# AirPi1-2.net
KiCad netlist of a schematic drawn in EAGLE
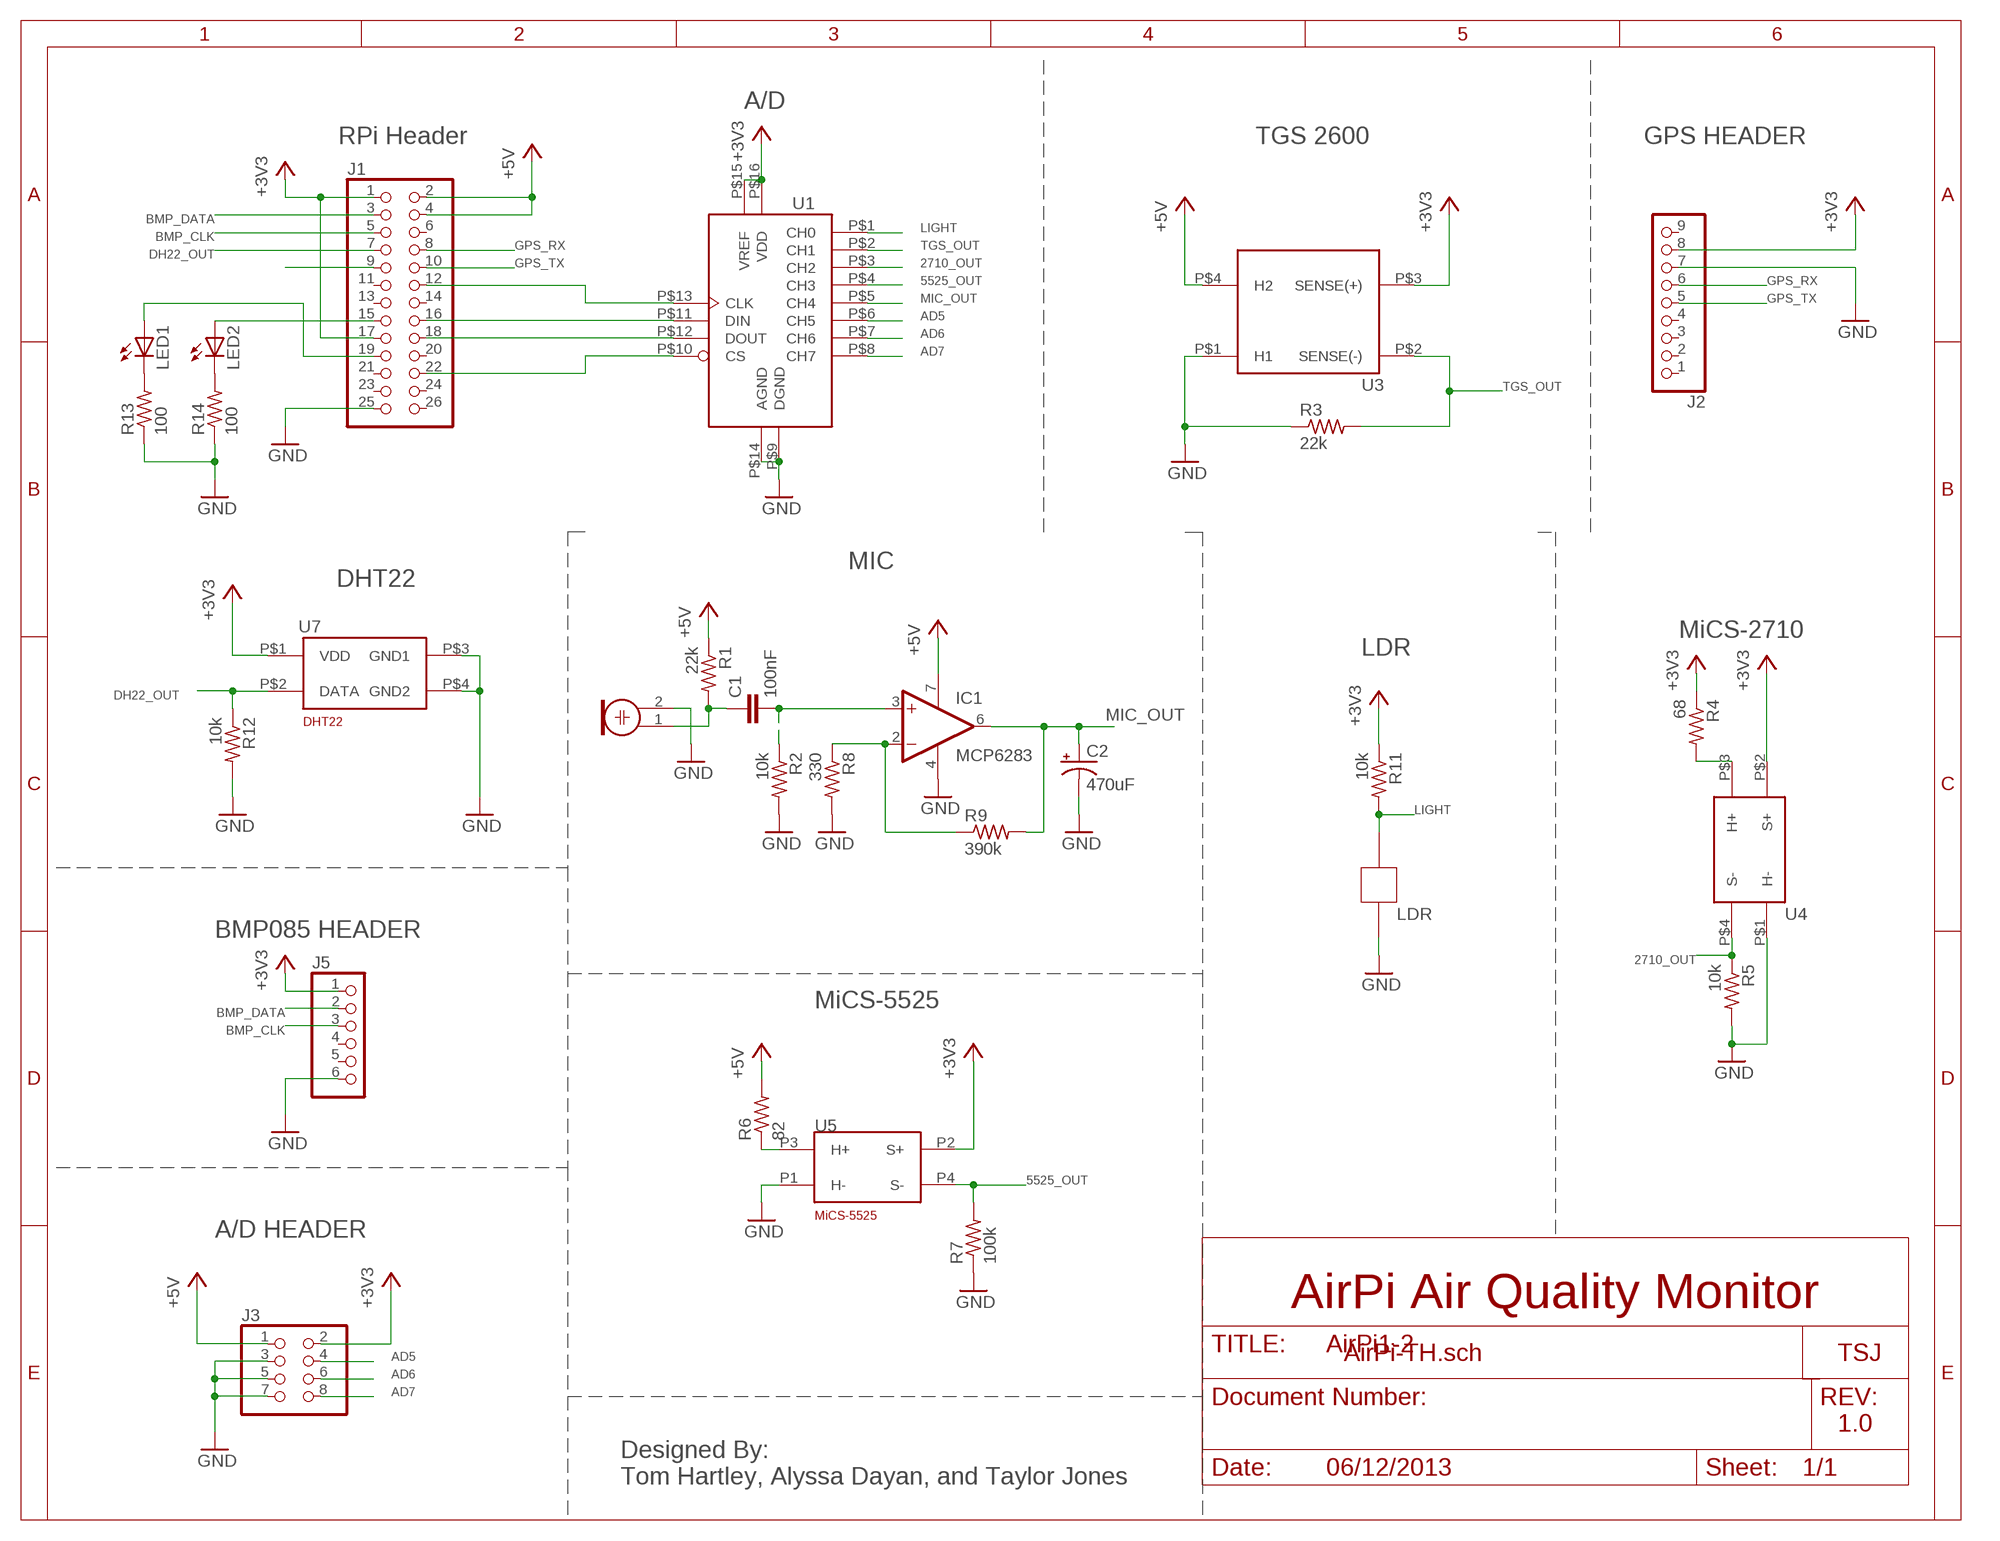
[diagram p0: schematic, sheet 1]

(export (version "E")
  (design (tool "Eeschema 10.0.6"))
  (components
    (comp (ref "C1")
      (value "100nF")
      (footprint "eagle-import:C2.5-4")
      (libsource (lib "eagle-import") (part "C2.5/4"))
    )
    (comp (ref "C2")
      (value "470uF")
      (footprint "eagle-import:E5-10,5")
      (libsource (lib "eagle-import") (part "CPOL-USE5-10.5"))
    )
    (comp (ref "IC1")
      (value "MCP6283")
      (footprint "eagle-import:DIL08")
      (libsource (lib "eagle-import") (part "OPAP344"))
    )
    (comp (ref "J1")
      (value "PINHD-2X13")
      (footprint "eagle-import:2X13")
      (libsource (lib "eagle-import") (part "PINHD-2X13"))
    )
    (comp (ref "J2")
      (value "PINHD-1X9")
      (footprint "eagle-import:1X09-BIG")
      (libsource (lib "eagle-import") (part "PINHD-1X9"))
    )
    (comp (ref "J3")
      (value "PINHD-2X4")
      (footprint "eagle-import:2X04")
      (libsource (lib "eagle-import") (part "PINHD-2X4"))
    )
    (comp (ref "J5")
      (value "PINHD-1X6")
      (footprint "eagle-import:1X06")
      (libsource (lib "eagle-import") (part "PINHD-1X6"))
    )
    (comp (ref "LDR1")
      (value "LDR")
      (footprint "eagle-import:LED5MM")
      (libsource (lib "eagle-import") (part "LDR"))
    )
    (comp (ref "LED1")
      (value "LED3MM")
      (footprint "eagle-import:LED3MM")
      (libsource (lib "eagle-import") (part "LED3MM"))
    )
    (comp (ref "LED2")
      (value "LED3MM")
      (footprint "eagle-import:LED3MM")
      (libsource (lib "eagle-import") (part "LED3MM"))
    )
    (comp (ref "M1")
      (value "MIC")
      (footprint "eagle-import:WM-62PC_62PK")
      (libsource (lib "eagle-import") (part "ELECTRET_MICROPHON-WM-62PC/62PK"))
    )
    (comp (ref "R1")
      (value "22k")
      (footprint "eagle-import:0207_10")
      (libsource (lib "eagle-import") (part "R-US_0207/10"))
    )
    (comp (ref "R2")
      (value "10k")
      (footprint "eagle-import:0207_10")
      (libsource (lib "eagle-import") (part "R-US_0207/10"))
    )
    (comp (ref "R3")
      (value "22k")
      (footprint "eagle-import:0207_10")
      (libsource (lib "eagle-import") (part "R-US_0207/10"))
    )
    (comp (ref "R4")
      (value "68")
      (footprint "eagle-import:0207_10")
      (libsource (lib "eagle-import") (part "R-US_0207/10"))
    )
    (comp (ref "R5")
      (value "10k")
      (footprint "eagle-import:0207_10")
      (libsource (lib "eagle-import") (part "R-US_0207/10"))
    )
    (comp (ref "R6")
      (value "82")
      (footprint "eagle-import:0207_10")
      (libsource (lib "eagle-import") (part "R-US_0207/10"))
    )
    (comp (ref "R7")
      (value "100k")
      (footprint "eagle-import:0207_10")
      (libsource (lib "eagle-import") (part "R-US_0207/10"))
    )
    (comp (ref "R8")
      (value "330")
      (footprint "eagle-import:0207_10")
      (libsource (lib "eagle-import") (part "R-US_0207/10"))
    )
    (comp (ref "R9")
      (value "390k")
      (footprint "eagle-import:0207_10")
      (libsource (lib "eagle-import") (part "R-US_0207/10"))
    )
    (comp (ref "R11")
      (value "10k")
      (footprint "eagle-import:0207_10")
      (libsource (lib "eagle-import") (part "R-US_0207/10"))
    )
    (comp (ref "R12")
      (value "10k")
      (footprint "eagle-import:0207_10")
      (libsource (lib "eagle-import") (part "R-US_0207/10"))
    )
    (comp (ref "R13")
      (value "100")
      (footprint "eagle-import:0207_10")
      (libsource (lib "eagle-import") (part "R-US_0207/10"))
    )
    (comp (ref "R14")
      (value "100")
      (footprint "eagle-import:0207_10")
      (libsource (lib "eagle-import") (part "R-US_0207/10"))
    )
    (comp (ref "U1")
      (value "MCP3008")
      (footprint "eagle-import:DIL16")
      (libsource (lib "eagle-import") (part "MCP30081"))
    )
    (comp (ref "U3")
      (value "TGS2600")
      (footprint "eagle-import:TGS2600")
      (libsource (lib "eagle-import") (part "TGS2600"))
    )
    (comp (ref "U4")
      (value "MICS-2710")
      (footprint "eagle-import:MICS-2710")
      (libsource (lib "eagle-import") (part "MICS-2710"))
    )
    (comp (ref "U5")
      (value "MICS-5525")
      (footprint "eagle-import:MICS-5525")
      (libsource (lib "eagle-import") (part "MICS-5525"))
    )
    (comp (ref "U7")
      (value "DHT22")
      (footprint "eagle-import:DHT22")
      (libsource (lib "eagle-import") (part "DHT22"))
    )
  )
  (nets
    (net (code "1") (name "+3V3") (class "Default")
      (node (ref "J1") (pin "1") (pinfunction "1_1") (pintype "passive"))
      (node (ref "J1") (pin "17") (pinfunction "17_17") (pintype "passive"))
      (node (ref "J2") (pin "8") (pinfunction "8_8") (pintype "passive"))
      (node (ref "J3") (pin "2") (pinfunction "2_2") (pintype "passive"))
      (node (ref "J5") (pin "1") (pinfunction "1_1") (pintype "passive"))
      (node (ref "R11") (pin "1") (pinfunction "1_1") (pintype "passive"))
      (node (ref "R4") (pin "1") (pinfunction "1_1") (pintype "passive"))
      (node (ref "U1") (pin "P$15") (pinfunction "VREF_P$15") (pintype "power_in"))
      (node (ref "U1") (pin "P$16") (pinfunction "VDD_P$16") (pintype "power_in"))
      (node (ref "U3") (pin "P$3") (pinfunction "SENSE(+)_P$3") (pintype "bidirectional"))
      (node (ref "U4") (pin "P$2") (pinfunction "S+_P$2") (pintype "bidirectional"))
      (node (ref "U5") (pin "P2") (pinfunction "S+_P2") (pintype "bidirectional"))
      (node (ref "U7") (pin "P$1") (pinfunction "VDD_P$1") (pintype "power_in"))
    )
    (net (code "2") (name "+5V") (class "Default")
      (node (ref "IC1") (pin "7") (pinfunction "V+_7") (pintype "power_in"))
      (node (ref "J1") (pin "2") (pinfunction "2_2") (pintype "passive"))
      (node (ref "J1") (pin "4") (pinfunction "4_4") (pintype "passive"))
      (node (ref "J3") (pin "1") (pinfunction "1_1") (pintype "passive"))
      (node (ref "R1") (pin "1") (pinfunction "1_1") (pintype "passive"))
      (node (ref "R6") (pin "2") (pinfunction "2_2") (pintype "passive"))
      (node (ref "U3") (pin "P$4") (pinfunction "H2_P$4") (pintype "power_in"))
    )
    (net (code "3") (name "/2710_OUT") (class "Default")
      (node (ref "R5") (pin "1") (pinfunction "1_1") (pintype "passive"))
      (node (ref "U1") (pin "P$3") (pinfunction "CH2_P$3") (pintype "input"))
      (node (ref "U4") (pin "P$4") (pinfunction "S-_P$4") (pintype "bidirectional"))
    )
    (net (code "4") (name "/5525_OUT") (class "Default")
      (node (ref "R7") (pin "2") (pinfunction "2_2") (pintype "passive"))
      (node (ref "U1") (pin "P$4") (pinfunction "CH3_P$4") (pintype "input"))
      (node (ref "U5") (pin "P4") (pinfunction "S-_P4") (pintype "bidirectional"))
    )
    (net (code "5") (name "/AD5") (class "Default")
      (node (ref "J3") (pin "4") (pinfunction "4_4") (pintype "passive"))
      (node (ref "U1") (pin "P$6") (pinfunction "CH5_P$6") (pintype "input"))
    )
    (net (code "6") (name "/AD6") (class "Default")
      (node (ref "J3") (pin "6") (pinfunction "6_6") (pintype "passive"))
      (node (ref "U1") (pin "P$7") (pinfunction "CH6_P$7") (pintype "input"))
    )
    (net (code "7") (name "/AD7") (class "Default")
      (node (ref "J3") (pin "8") (pinfunction "8_8") (pintype "passive"))
      (node (ref "U1") (pin "P$8") (pinfunction "CH7_P$8") (pintype "input"))
    )
    (net (code "8") (name "/BMP_CLK") (class "Default")
      (node (ref "J1") (pin "5") (pinfunction "5_5") (pintype "passive"))
      (node (ref "J5") (pin "3") (pinfunction "3_3") (pintype "passive"))
    )
    (net (code "9") (name "/BMP_DATA") (class "Default")
      (node (ref "J1") (pin "3") (pinfunction "3_3") (pintype "passive"))
      (node (ref "J5") (pin "2") (pinfunction "2_2") (pintype "passive"))
    )
    (net (code "10") (name "/DH22_OUT") (class "Default")
      (node (ref "J1") (pin "7") (pinfunction "7_7") (pintype "passive"))
      (node (ref "R12") (pin "1") (pinfunction "1_1") (pintype "passive"))
      (node (ref "U7") (pin "P$2") (pinfunction "DATA_P$2") (pintype "bidirectional"))
    )
    (net (code "11") (name "/GPS_RX") (class "Default")
      (node (ref "J1") (pin "8") (pinfunction "8_8") (pintype "passive"))
      (node (ref "J2") (pin "6") (pinfunction "6_6") (pintype "passive"))
    )
    (net (code "12") (name "/GPS_TX") (class "Default")
      (node (ref "J1") (pin "10") (pinfunction "10_10") (pintype "passive"))
      (node (ref "J2") (pin "5") (pinfunction "5_5") (pintype "passive"))
    )
    (net (code "13") (name "/LIGHT") (class "Default")
      (node (ref "LDR1") (pin "A") (pinfunction "P$1_A") (pintype "bidirectional"))
      (node (ref "R11") (pin "2") (pinfunction "2_2") (pintype "passive"))
      (node (ref "U1") (pin "P$1") (pinfunction "CH0_P$1") (pintype "input"))
    )
    (net (code "14") (name "/MIC_OUT") (class "Default")
      (node (ref "C2") (pin "+") (pinfunction "+_+") (pintype "passive"))
      (node (ref "IC1") (pin "6") (pinfunction "OUT_6") (pintype "output"))
      (node (ref "R9") (pin "2") (pinfunction "2_2") (pintype "passive"))
      (node (ref "U1") (pin "P$5") (pinfunction "CH4_P$5") (pintype "input"))
    )
    (net (code "15") (name "/TGS_OUT") (class "Default")
      (node (ref "R3") (pin "2") (pinfunction "2_2") (pintype "passive"))
      (node (ref "U1") (pin "P$2") (pinfunction "CH1_P$2") (pintype "input"))
      (node (ref "U3") (pin "P$2") (pinfunction "SENSE(-)_P$2") (pintype "bidirectional"))
    )
    (net (code "16") (name "GND") (class "Default")
      (node (ref "C2") (pin "-") (pinfunction "-_-") (pintype "passive"))
      (node (ref "IC1") (pin "4") (pinfunction "V-_4") (pintype "power_in"))
      (node (ref "J1") (pin "25") (pinfunction "25_25") (pintype "passive"))
      (node (ref "J2") (pin "7") (pinfunction "7_7") (pintype "passive"))
      (node (ref "J3") (pin "3") (pinfunction "3_3") (pintype "passive"))
      (node (ref "J3") (pin "5") (pinfunction "5_5") (pintype "passive"))
      (node (ref "J3") (pin "7") (pinfunction "7_7") (pintype "passive"))
      (node (ref "J5") (pin "6") (pinfunction "6_6") (pintype "passive"))
      (node (ref "LDR1") (pin "K") (pinfunction "P$2_K") (pintype "bidirectional"))
      (node (ref "M1") (pin "2") (pinfunction "2_2") (pintype "passive"))
      (node (ref "R12") (pin "2") (pinfunction "2_2") (pintype "passive"))
      (node (ref "R13") (pin "1") (pinfunction "1_1") (pintype "passive"))
      (node (ref "R14") (pin "1") (pinfunction "1_1") (pintype "passive"))
      (node (ref "R2") (pin "2") (pinfunction "2_2") (pintype "passive"))
      (node (ref "R3") (pin "1") (pinfunction "1_1") (pintype "passive"))
      (node (ref "R5") (pin "2") (pinfunction "2_2") (pintype "passive"))
      (node (ref "R7") (pin "1") (pinfunction "1_1") (pintype "passive"))
      (node (ref "R8") (pin "2") (pinfunction "2_2") (pintype "passive"))
      (node (ref "U1") (pin "P$14") (pinfunction "AGND_P$14") (pintype "power_in"))
      (node (ref "U1") (pin "P$9") (pinfunction "DGND_P$9") (pintype "power_in"))
      (node (ref "U3") (pin "P$1") (pinfunction "H1_P$1") (pintype "power_in"))
      (node (ref "U4") (pin "P$1") (pinfunction "H-_P$1") (pintype "power_in"))
      (node (ref "U5") (pin "P1") (pinfunction "H-_P1") (pintype "power_in"))
      (node (ref "U7") (pin "P$3") (pinfunction "GND1_P$3") (pintype "power_in"))
      (node (ref "U7") (pin "P$4") (pinfunction "GND2_P$4") (pintype "bidirectional"))
    )
    (net (code "17") (name "Net-(C1-Pad1)") (class "Default")
      (node (ref "C1") (pin "1") (pinfunction "1_1") (pintype "passive"))
      (node (ref "M1") (pin "1") (pinfunction "1_1") (pintype "passive"))
      (node (ref "R1") (pin "2") (pinfunction "2_2") (pintype "passive"))
    )
    (net (code "18") (name "Net-(IC1-+IN)") (class "Default")
      (node (ref "C1") (pin "2") (pinfunction "2_2") (pintype "passive"))
      (node (ref "IC1") (pin "3") (pinfunction "+IN_3") (pintype "input"))
      (node (ref "R2") (pin "1") (pinfunction "1_1") (pintype "passive"))
    )
    (net (code "19") (name "Net-(IC1--IN)") (class "Default")
      (node (ref "IC1") (pin "2") (pinfunction "-IN_2") (pintype "input"))
      (node (ref "R8") (pin "1") (pinfunction "1_1") (pintype "passive"))
      (node (ref "R9") (pin "1") (pinfunction "1_1") (pintype "passive"))
    )
    (net (code "20") (name "Net-(J1-Pad15)") (class "Default")
      (node (ref "J1") (pin "15") (pinfunction "15_15") (pintype "passive"))
      (node (ref "LED2") (pin "A") (pinfunction "A_A") (pintype "passive"))
    )
    (net (code "21") (name "Net-(J1-Pad19)") (class "Default")
      (node (ref "J1") (pin "19") (pinfunction "19_19") (pintype "passive"))
      (node (ref "LED1") (pin "A") (pinfunction "A_A") (pintype "passive"))
    )
    (net (code "22") (name "Net-(LED1-C)") (class "Default")
      (node (ref "LED1") (pin "K") (pinfunction "C_K") (pintype "passive"))
      (node (ref "R13") (pin "2") (pinfunction "2_2") (pintype "passive"))
    )
    (net (code "23") (name "Net-(LED2-C)") (class "Default")
      (node (ref "LED2") (pin "K") (pinfunction "C_K") (pintype "passive"))
      (node (ref "R14") (pin "2") (pinfunction "2_2") (pintype "passive"))
    )
    (net (code "24") (name "Net-(U1-CLK)") (class "Default")
      (node (ref "J1") (pin "12") (pinfunction "12_12") (pintype "passive"))
      (node (ref "U1") (pin "P$13") (pinfunction "CLK_P$13") (pintype "input"))
    )
    (net (code "25") (name "Net-(U1-CS)") (class "Default")
      (node (ref "J1") (pin "22") (pinfunction "22_22") (pintype "passive"))
      (node (ref "U1") (pin "P$10") (pinfunction "CS_P$10") (pintype "input"))
    )
    (net (code "26") (name "Net-(U1-DIN)") (class "Default")
      (node (ref "J1") (pin "16") (pinfunction "16_16") (pintype "passive"))
      (node (ref "U1") (pin "P$11") (pinfunction "DIN_P$11") (pintype "input"))
    )
    (net (code "27") (name "Net-(U1-DOUT)") (class "Default")
      (node (ref "J1") (pin "18") (pinfunction "18_18") (pintype "passive"))
      (node (ref "U1") (pin "P$12") (pinfunction "DOUT_P$12") (pintype "output"))
    )
    (net (code "28") (name "Net-(U4-H+)") (class "Default")
      (node (ref "R4") (pin "2") (pinfunction "2_2") (pintype "passive"))
      (node (ref "U4") (pin "P$3") (pinfunction "H+_P$3") (pintype "power_in"))
    )
    (net (code "29") (name "Net-(U5-H+)") (class "Default")
      (node (ref "R6") (pin "1") (pinfunction "1_1") (pintype "passive"))
      (node (ref "U5") (pin "P3") (pinfunction "H+_P3") (pintype "power_in"))
    )
    (net (code "30") (name "unconnected-(J1-Pad6)") (class "Default")
      (node (ref "J1") (pin "6") (pinfunction "6_6") (pintype "passive"))
    )
    (net (code "31") (name "unconnected-(J1-Pad9)") (class "Default")
      (node (ref "J1") (pin "9") (pinfunction "9_9") (pintype "passive"))
    )
    (net (code "32") (name "unconnected-(J1-Pad11)") (class "Default")
      (node (ref "J1") (pin "11") (pinfunction "11_11") (pintype "passive"))
    )
    (net (code "33") (name "unconnected-(J1-Pad13)") (class "Default")
      (node (ref "J1") (pin "13") (pinfunction "13_13") (pintype "passive"))
    )
    (net (code "34") (name "unconnected-(J1-Pad14)") (class "Default")
      (node (ref "J1") (pin "14") (pinfunction "14_14") (pintype "passive"))
    )
    (net (code "35") (name "unconnected-(J1-Pad20)") (class "Default")
      (node (ref "J1") (pin "20") (pinfunction "20_20") (pintype "passive"))
    )
    (net (code "36") (name "unconnected-(J1-Pad21)") (class "Default")
      (node (ref "J1") (pin "21") (pinfunction "21_21") (pintype "passive"))
    )
    (net (code "37") (name "unconnected-(J1-Pad23)") (class "Default")
      (node (ref "J1") (pin "23") (pinfunction "23_23") (pintype "passive"))
    )
    (net (code "38") (name "unconnected-(J1-Pad24)") (class "Default")
      (node (ref "J1") (pin "24") (pinfunction "24_24") (pintype "passive"))
    )
    (net (code "39") (name "unconnected-(J1-Pad26)") (class "Default")
      (node (ref "J1") (pin "26") (pinfunction "26_26") (pintype "passive"))
    )
    (net (code "40") (name "unconnected-(J2-Pad1)") (class "Default")
      (node (ref "J2") (pin "1") (pinfunction "1_1") (pintype "passive"))
    )
    (net (code "41") (name "unconnected-(J2-Pad2)") (class "Default")
      (node (ref "J2") (pin "2") (pinfunction "2_2") (pintype "passive"))
    )
    (net (code "42") (name "unconnected-(J2-Pad3)") (class "Default")
      (node (ref "J2") (pin "3") (pinfunction "3_3") (pintype "passive"))
    )
    (net (code "43") (name "unconnected-(J2-Pad4)") (class "Default")
      (node (ref "J2") (pin "4") (pinfunction "4_4") (pintype "passive"))
    )
    (net (code "44") (name "unconnected-(J2-Pad9)") (class "Default")
      (node (ref "J2") (pin "9") (pinfunction "9_9") (pintype "passive"))
    )
    (net (code "45") (name "unconnected-(J5-Pad4)") (class "Default")
      (node (ref "J5") (pin "4") (pinfunction "4_4") (pintype "passive"))
    )
    (net (code "46") (name "unconnected-(J5-Pad5)") (class "Default")
      (node (ref "J5") (pin "5") (pinfunction "5_5") (pintype "passive"))
    )
  )
)
